# 1_FET_A.net
KiCad netlist of a schematic drawn in Altium Designer
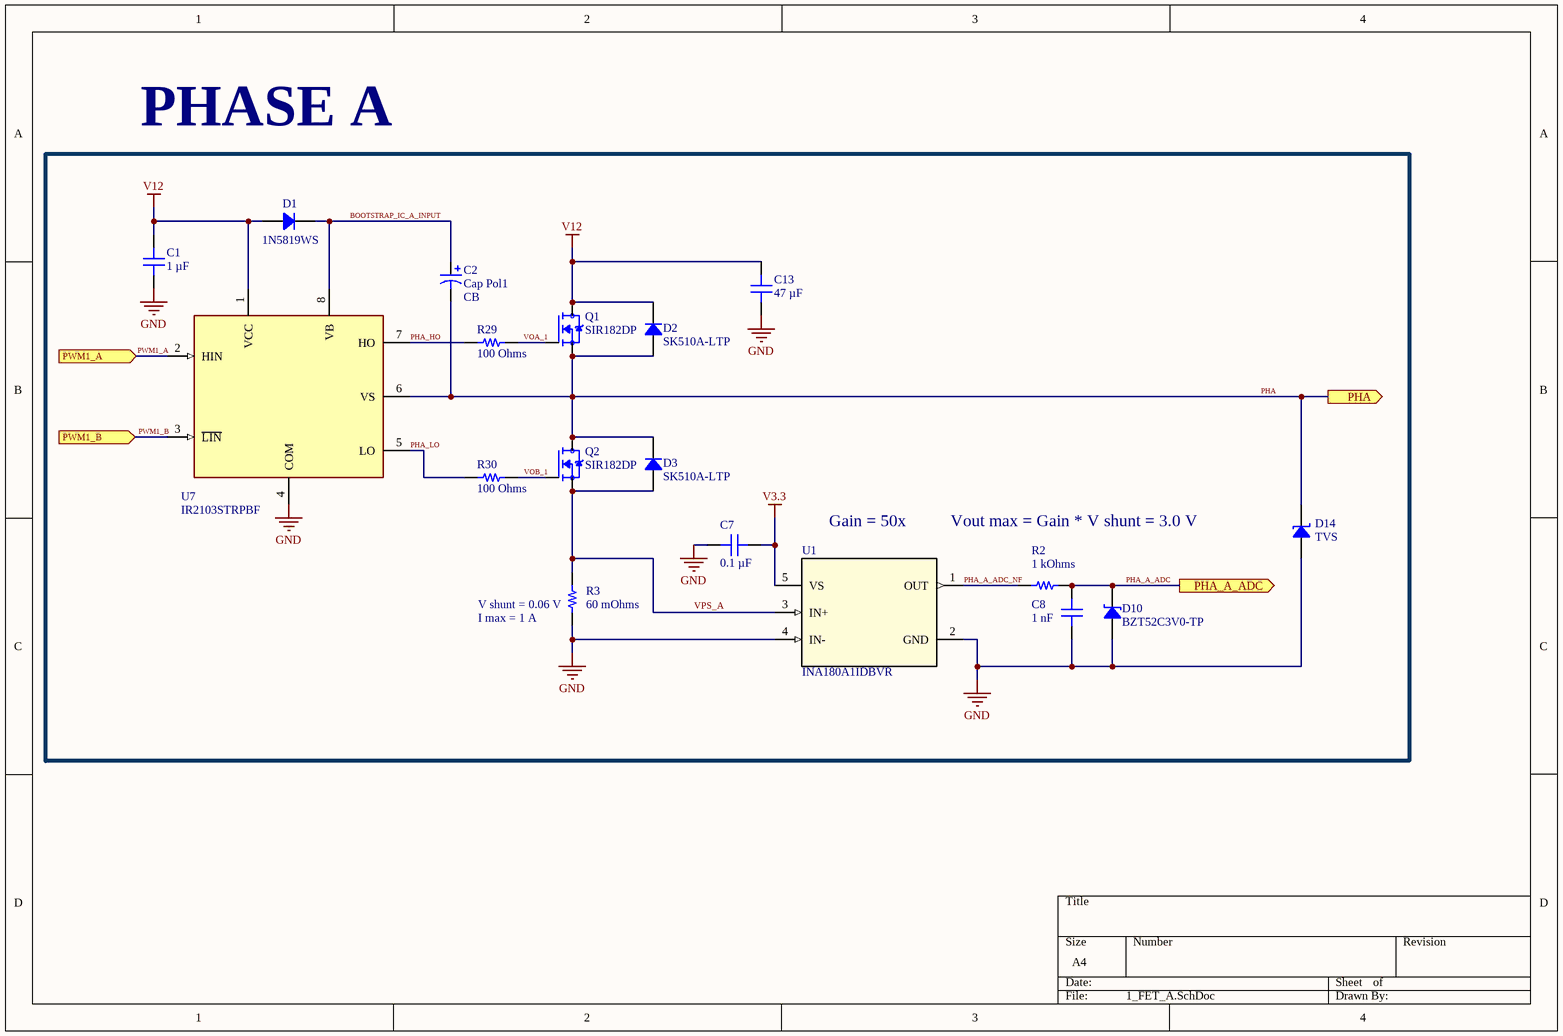
[diagram p0: 1_FET_A.SchDoc]

(export (version "E")
  (design (tool "Eeschema 10.0.6"))
  (components
    (comp (ref "C1")
      (value "1 µF")
      (footprint "CAP 0805_2012")
      (description "CAP CER 0.1UF 50V X7R 0805")
      (fields (field (name "PART NUMBER") "CC0805MRX7R9BB104") (field (name "MANUFACTURER") "Yageo"))
      (libsource (lib "Celestial Altium Library - altium_library") (part "Capacitor"))
    )
    (comp (ref "C2")
      (value "Cap Pol1")
      (footprint "CapacitorRadialElectrolytic")
      (description "Polarized Capacitor (Radial)")
      (fields (field (name "ALTIUM_VALUE") "CB") (field (name "PUBLISHER") "Altium Limited"))
      (libsource (lib "Miscellaneous Devices") (part "Cap Pol1"))
    )
    (comp (ref "C7")
      (value "0.1 µF")
      (footprint "CAP 0805_2012")
      (description "CAP CER 0.1UF 50V X7R 0805")
      (fields (field (name "PART NUMBER") "CC0805MRX7R9BB104") (field (name "MANUFACTURER") "Yageo"))
      (libsource (lib "Celestial Altium Library - altium_library") (part "Capacitor"))
    )
    (comp (ref "C8")
      (value "1 nF")
      (footprint "CAP 0805_2012")
      (description "CAP CER 0.1UF 50V X7R 0805")
      (fields (field (name "PART NUMBER") "CC0805MRX7R9BB104") (field (name "MANUFACTURER") "Yageo"))
      (libsource (lib "Celestial Altium Library - altium_library") (part "Capacitor"))
    )
    (comp (ref "C13")
      (value "47 µF")
      (footprint "CAP 1812_4532 1.1MM")
      (description "CAP1812 X5R 47UF 20% 6.3V")
      (fields
        (field (name "PART NUMBER") "GMC43X5R476M6R3NT")
        (field (name "MANUFACTURER") "Cal-Chip Electronics, Inc.")
      )
      (libsource (lib "Celestial Altium Library - altium_library") (part "Capacitor"))
    )
    (comp (ref "D1")
      (value "1N5819WS")
      (footprint "SOD-123")
      (description "DIODE SCHOTTKY 40V 1A SOD123")
      (fields (field (name "PART NUMBER") "1N5819HW-7-F") (field (name "MANUFACTURER") "Diodes Incorporated"))
      (libsource (lib "Celestial Altium Library - altium_library") (part "Diode"))
    )
    (comp (ref "D2")
      (value "SK510A-LTP")
      (footprint "DO214AC SMA")
      (description "DIODE SCHOTTKY 100V 5A DO214AC")
      (fields (field (name "MANUFACTURER") "Micro Commercial Co"))
      (libsource (lib "Celestial Altium Library - altium_library") (part "Diode"))
    )
    (comp (ref "D3")
      (value "SK510A-LTP")
      (footprint "DO214AC SMA")
      (description "DIODE SCHOTTKY 100V 5A DO214AC")
      (fields (field (name "MANUFACTURER") "Micro Commercial Co"))
      (libsource (lib "Celestial Altium Library - altium_library") (part "Diode"))
    )
    (comp (ref "D10")
      (value "BZT52C3V0-TP")
      (footprint "SOD-123")
      (description "DIODE ZENER 3V 200MW SOD123")
      (fields (field (name "MANUFACTURER") "Micro Commercial Co") (field (name "TOLERANCE") "±7%"))
      (libsource (lib "Celestial Altium Library - altium_library") (part "Diode Zener"))
    )
    (comp (ref "D14")
      (value "TVS")
      (footprint "SMF DO-219AB")
      (description "TVS DIODE 57.6V 98V DO219AB")
      (fields
        (field (name "PART NUMBER") "VTVS58ASMF-HM3-08")
        (field (name "MANUFACTURER") "Vishay Semiconductor Diodes Division")
      )
      (libsource (lib "Celestial Altium Library - altium_library") (part "DIODE TVS UNI"))
    )
    (comp (ref "Q1")
      (value "SIR182DP")
      (footprint "TRANS_SIR182DP-T1-RE3")
      (description "N-Channel 60V 60A _Tc_ 69.4W _Tc_ Surface Mount PowerPAKÂ® SO-8")
      (fields (field (name "MP") "SIR182DP-T1-RE3") (field (name "MF") "Vishay Siliconix"))
      (libsource (lib "BLDC_BridgeBoard_V1") (part "SIR182DP-T1-RE3"))
    )
    (comp (ref "Q2")
      (value "SIR182DP")
      (footprint "TRANS_SIR182DP-T1-RE3")
      (description "N-Channel 60V 60A _Tc_ 69.4W _Tc_ Surface Mount PowerPAKÂ® SO-8")
      (fields (field (name "MP") "SIR182DP-T1-RE3") (field (name "MF") "Vishay Siliconix"))
      (libsource (lib "BLDC_BridgeBoard_V1") (part "SIR182DP-T1-RE3"))
    )
    (comp (ref "R2")
      (value "1 kOhms")
      (footprint "RES 0805_2012")
      (description "RES SMD 200K OHM 5% 1/8W 0805")
      (fields (field (name "PART NUMBER") "CR0805-JW-204ELF") (field (name "MANUFACTURER") "Bourns Inc."))
      (libsource (lib "Celestial Altium Library - altium_library") (part "Resistor"))
    )
    (comp (ref "R3")
      (value "60 mOhms")
      (footprint "STACKPOLE CSR2512")
      (description "RES SMD 500 UOHM 1% 3W 2512")
      (fields (field (name "PART NUMBER") "CSR2512C0R0005F") (field (name "MANUFACTURER") "Riedon"))
      (libsource (lib "Celestial Altium Library - altium_library") (part "Resistor"))
    )
    (comp (ref "R29")
      (value "100 Ohms")
      (footprint "RES 0805_2012")
      (description "RES SMD 4.7K OHM 5% 1/2W 0805")
      (fields (field (name "PART NUMBER") "RCS08054K70JNEA") (field (name "MANUFACTURER") "Vishay Dale"))
      (libsource (lib "Celestial Altium Library - altium_library") (part "Resistor"))
    )
    (comp (ref "R30")
      (value "100 Ohms")
      (footprint "RES 0805_2012")
      (description "RES SMD 4.7K OHM 5% 1/2W 0805")
      (fields (field (name "PART NUMBER") "RCS08054K70JNEA") (field (name "MANUFACTURER") "Vishay Dale"))
      (libsource (lib "Celestial Altium Library - altium_library") (part "Resistor"))
    )
    (comp (ref "U1")
      (value "INA180A1IDBVR")
      (footprint "DBV0005A_N")
      (description "No Description Available")
      (fields (field (name "COPYRIGHT") "Copyright (C) 2023 Ultra Librarian. All rights reserved."))
      (libsource (lib "INA180A1IDBVR") (part "INA180A1IDBVR"))
    )
    (comp (ref "U7")
      (value "IR2103STRPBF")
      (footprint "Milibreria:SOIC8_IR2103STRPBF")
      (fields (field (name "MF") "Infineon"))
      (libsource (lib "BLDC_BridgeBoard_V1") (part "IR2103STRPBF"))
    )
  )
  (nets
    (net (code "1") (name "/BOOTSTRAP_IC_A_INPUT") (class "Default")
      (node (ref "C2") (pin "1") (pinfunction "1_1") (pintype "passive"))
      (node (ref "D1") (pin "2") (pinfunction "2_2") (pintype "passive"))
      (node (ref "U7") (pin "8") (pinfunction "VB_8") (pintype "power_in"))
    )
    (net (code "2") (name "/PHA") (class "Default")
      (node (ref "C2") (pin "2") (pinfunction "2_2") (pintype "passive"))
      (node (ref "D14") (pin "2") (pinfunction "2_2") (pintype "passive"))
      (node (ref "D2") (pin "1") (pinfunction "1_1") (pintype "passive"))
      (node (ref "D3") (pin "2") (pinfunction "2_2") (pintype "passive"))
      (node (ref "Q1") (pin "1") (pinfunction "S_1") (pintype "passive"))
      (node (ref "Q1") (pin "2") (pinfunction "S_2") (pintype "passive"))
      (node (ref "Q1") (pin "3") (pinfunction "S_3") (pintype "passive"))
      (node (ref "Q2") (pin "5") (pinfunction "D_5") (pintype "passive"))
      (node (ref "Q2") (pin "6") (pinfunction "D_6") (pintype "passive"))
      (node (ref "Q2") (pin "7") (pinfunction "D_7") (pintype "passive"))
      (node (ref "Q2") (pin "8") (pinfunction "D_8") (pintype "passive"))
      (node (ref "Q2") (pin "9") (pinfunction "D_9") (pintype "passive"))
      (node (ref "U7") (pin "6") (pinfunction "VS_6") (pintype "passive"))
    )
    (net (code "3") (name "/PHA_A_ADC") (class "Default")
      (node (ref "C8") (pin "1") (pinfunction "1_1") (pintype "passive"))
      (node (ref "D10") (pin "2") (pinfunction "2_2") (pintype "passive"))
      (node (ref "R2") (pin "2") (pinfunction "2_2") (pintype "passive"))
    )
    (net (code "4") (name "/PHA_A_ADC_NF") (class "Default")
      (node (ref "R2") (pin "1") (pinfunction "1_1") (pintype "passive"))
      (node (ref "U1") (pin "1") (pinfunction "OUT_1") (pintype "output"))
    )
    (net (code "5") (name "/PHA_HO") (class "Default")
      (node (ref "R29") (pin "2") (pinfunction "2_2") (pintype "passive"))
      (node (ref "U7") (pin "7") (pinfunction "HO_7") (pintype "passive"))
    )
    (net (code "6") (name "/PHA_LO") (class "Default")
      (node (ref "R30") (pin "2") (pinfunction "2_2") (pintype "passive"))
      (node (ref "U7") (pin "5") (pinfunction "LO_5") (pintype "passive"))
    )
    (net (code "7") (name "/PWM1_A") (class "Default")
      (node (ref "U7") (pin "2") (pinfunction "HIN_2") (pintype "input"))
    )
    (net (code "8") (name "/PWM1_B") (class "Default")
      (node (ref "U7") (pin "3") (pinfunction "~{LIN}_3") (pintype "input"))
    )
    (net (code "9") (name "/VOA_1") (class "Default")
      (node (ref "Q1") (pin "4") (pinfunction "G_4") (pintype "passive"))
      (node (ref "R29") (pin "1") (pinfunction "1_1") (pintype "passive"))
    )
    (net (code "10") (name "/VOB_1") (class "Default")
      (node (ref "Q2") (pin "4") (pinfunction "G_4") (pintype "passive"))
      (node (ref "R30") (pin "1") (pinfunction "1_1") (pintype "passive"))
    )
    (net (code "11") (name "/VPS_A") (class "Default")
      (node (ref "D3") (pin "1") (pinfunction "1_1") (pintype "passive"))
      (node (ref "Q2") (pin "1") (pinfunction "S_1") (pintype "passive"))
      (node (ref "Q2") (pin "2") (pinfunction "S_2") (pintype "passive"))
      (node (ref "Q2") (pin "3") (pinfunction "S_3") (pintype "passive"))
      (node (ref "R3") (pin "2") (pinfunction "2_2") (pintype "passive"))
      (node (ref "U1") (pin "3") (pinfunction "IN+_3") (pintype "input"))
    )
    (net (code "12") (name "GND") (class "Default")
      (node (ref "C1") (pin "1") (pinfunction "1_1") (pintype "passive"))
      (node (ref "C13") (pin "1") (pinfunction "1_1") (pintype "passive"))
      (node (ref "C7") (pin "2") (pinfunction "2_2") (pintype "passive"))
      (node (ref "C8") (pin "2") (pinfunction "2_2") (pintype "passive"))
      (node (ref "D10") (pin "1") (pinfunction "1_1") (pintype "passive"))
      (node (ref "D14") (pin "1") (pinfunction "1_1") (pintype "passive"))
      (node (ref "R3") (pin "1") (pinfunction "1_1") (pintype "passive"))
      (node (ref "U1") (pin "2") (pinfunction "GND_2") (pintype "power_in"))
      (node (ref "U1") (pin "4") (pinfunction "IN-_4") (pintype "input"))
      (node (ref "U7") (pin "4") (pinfunction "COM_4") (pintype "power_in"))
    )
    (net (code "13") (name "V3.3") (class "Default")
      (node (ref "C7") (pin "1") (pinfunction "1_1") (pintype "passive"))
      (node (ref "U1") (pin "5") (pinfunction "VS_5") (pintype "power_in"))
    )
    (net (code "14") (name "V12") (class "Default")
      (node (ref "C1") (pin "2") (pinfunction "2_2") (pintype "passive"))
      (node (ref "C13") (pin "2") (pinfunction "2_2") (pintype "passive"))
      (node (ref "D1") (pin "1") (pinfunction "1_1") (pintype "passive"))
      (node (ref "D2") (pin "2") (pinfunction "2_2") (pintype "passive"))
      (node (ref "Q1") (pin "5") (pinfunction "D_5") (pintype "passive"))
      (node (ref "Q1") (pin "6") (pinfunction "D_6") (pintype "passive"))
      (node (ref "Q1") (pin "7") (pinfunction "D_7") (pintype "passive"))
      (node (ref "Q1") (pin "8") (pinfunction "D_8") (pintype "passive"))
      (node (ref "Q1") (pin "9") (pinfunction "D_9") (pintype "passive"))
      (node (ref "U7") (pin "1") (pinfunction "VCC_1") (pintype "power_in"))
    )
  )
)
